# Controller.net
KiCad netlist of a schematic drawn in Altium Designer
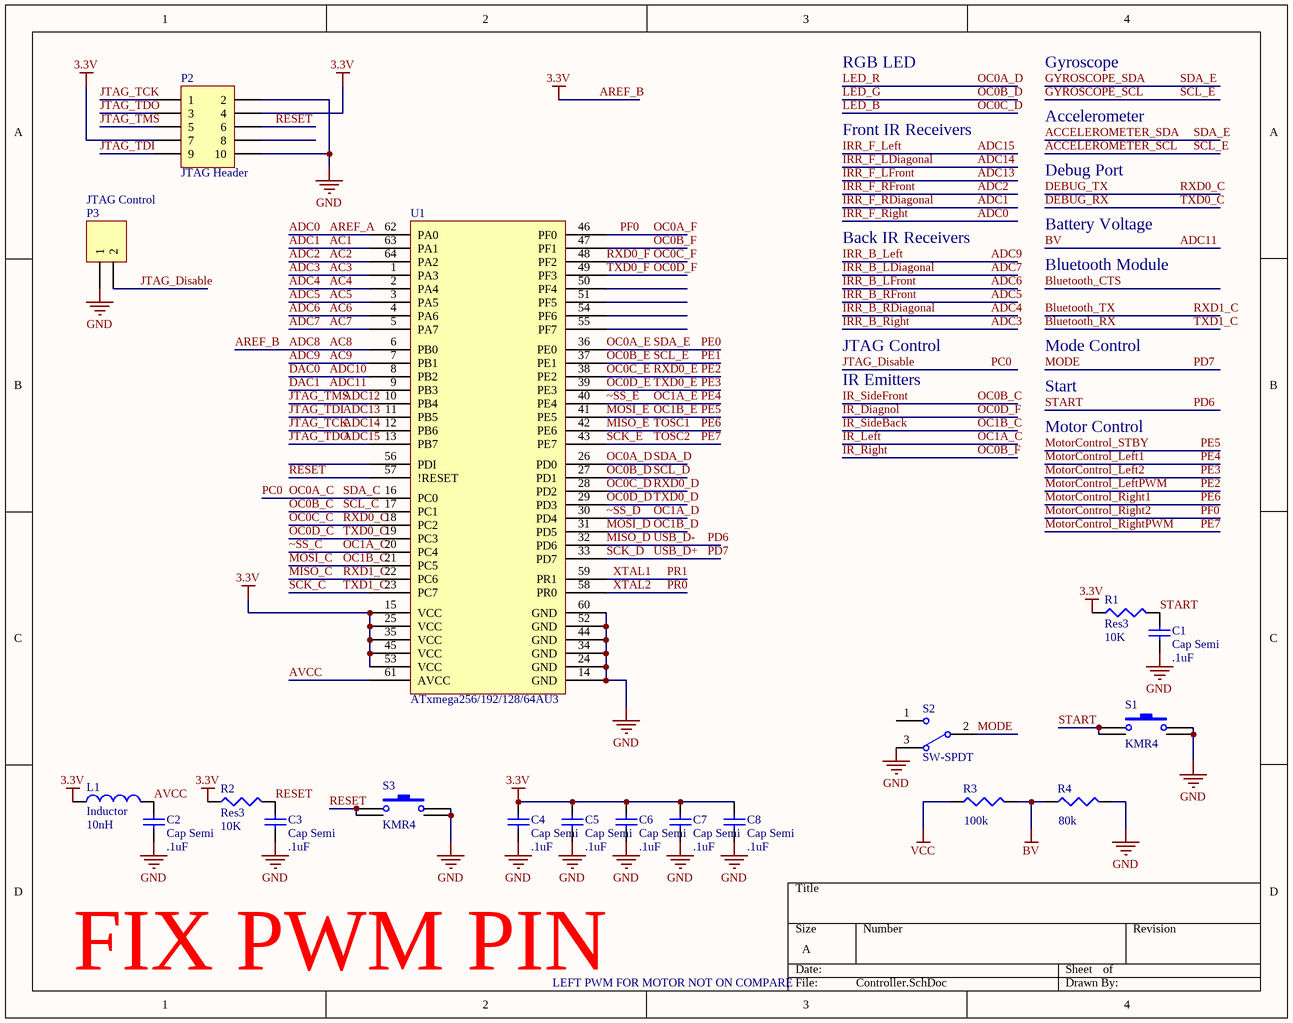
[diagram p0: Controller.SchDoc]

(export (version "E")
  (design (tool "Eeschema 10.0.6"))
  (components
    (comp (ref "C1")
      (value "Cap Semi")
      (footprint "1608[0603]")
      (description "Capacitor (Semiconductor SIM Model)")
      (fields (field (name "ALTIUM_VALUE") ".1uF") (field (name "PUBLISHER") "Altium Limited"))
      (libsource (lib "Miscellaneous Devices") (part "Cap Semi"))
    )
    (comp (ref "C2")
      (value "Cap Semi")
      (footprint "1608[0603]")
      (description "Capacitor (Semiconductor SIM Model)")
      (fields (field (name "ALTIUM_VALUE") ".1uF") (field (name "PUBLISHER") "Altium Limited"))
      (libsource (lib "Miscellaneous Devices") (part "Cap Semi"))
    )
    (comp (ref "C3")
      (value "Cap Semi")
      (footprint "1608[0603]")
      (description "Capacitor (Semiconductor SIM Model)")
      (fields (field (name "ALTIUM_VALUE") ".1uF") (field (name "PUBLISHER") "Altium Limited"))
      (libsource (lib "Miscellaneous Devices") (part "Cap Semi"))
    )
    (comp (ref "C4")
      (value "Cap Semi")
      (footprint "1608[0603]")
      (description "Capacitor (Semiconductor SIM Model)")
      (fields (field (name "ALTIUM_VALUE") ".1uF") (field (name "PUBLISHER") "Altium Limited"))
      (libsource (lib "Miscellaneous Devices") (part "Cap Semi"))
    )
    (comp (ref "C5")
      (value "Cap Semi")
      (footprint "1608[0603]")
      (description "Capacitor (Semiconductor SIM Model)")
      (fields (field (name "ALTIUM_VALUE") ".1uF") (field (name "PUBLISHER") "Altium Limited"))
      (libsource (lib "Miscellaneous Devices") (part "Cap Semi"))
    )
    (comp (ref "C6")
      (value "Cap Semi")
      (footprint "1608[0603]")
      (description "Capacitor (Semiconductor SIM Model)")
      (fields (field (name "ALTIUM_VALUE") ".1uF") (field (name "PUBLISHER") "Altium Limited"))
      (libsource (lib "Miscellaneous Devices") (part "Cap Semi"))
    )
    (comp (ref "C7")
      (value "Cap Semi")
      (footprint "1608[0603]")
      (description "Capacitor (Semiconductor SIM Model)")
      (fields (field (name "ALTIUM_VALUE") ".1uF") (field (name "PUBLISHER") "Altium Limited"))
      (libsource (lib "Miscellaneous Devices") (part "Cap Semi"))
    )
    (comp (ref "C8")
      (value "Cap Semi")
      (footprint "1608[0603]")
      (description "Capacitor (Semiconductor SIM Model)")
      (fields (field (name "ALTIUM_VALUE") ".1uF") (field (name "PUBLISHER") "Altium Limited"))
      (libsource (lib "Miscellaneous Devices") (part "Cap Semi"))
    )
    (comp (ref "L1")
      (value "Inductor")
      (footprint "INDC1608L")
      (fields (field (name "ALTIUM_VALUE") "10nH") (field (name "PUBLISHER") "Altium Limited"))
      (libsource (lib "Miscellaneous Devices") (part "Inductor"))
    )
    (comp (ref "P2")
      (value "JTAG Header")
      (footprint "HDR2X5")
      (description "Header, 5-Pin, Dual row")
      (fields (field (name "PUBLISHER") "Altium Limited"))
      (libsource (lib "Miscellaneous Connectors") (part "Header 5X2"))
    )
    (comp (ref "P3")
      (value "JTAG Control")
      (footprint "HDR1X2")
      (description "Header, 2-Pin")
      (fields (field (name "PUBLISHER") "Altium Limited"))
      (libsource (lib "Miscellaneous Connectors") (part "Header 2"))
    )
    (comp (ref "R1")
      (value "Res3")
      (footprint "J1-0603")
      (description "Resistor")
      (fields (field (name "ALTIUM_VALUE") "10K") (field (name "PUBLISHER") "Altium Limited"))
      (libsource (lib "Miscellaneous Devices") (part "Res3"))
    )
    (comp (ref "R2")
      (value "Res3")
      (footprint "J1-0603")
      (description "Resistor")
      (fields (field (name "ALTIUM_VALUE") "10K") (field (name "PUBLISHER") "Altium Limited"))
      (libsource (lib "Miscellaneous Devices") (part "Res3"))
    )
    (comp (ref "R3")
      (value "100k")
      (footprint "J1-0603")
      (description "Resistor")
      (fields (field (name "Comment") "Res3") (field (name "PUBLISHER") "Altium Limited"))
      (libsource (lib "Miscellaneous Devices") (part "Res3"))
    )
    (comp (ref "R4")
      (value "80k")
      (footprint "J1-0603")
      (description "Resistor")
      (fields (field (name "Comment") "Res3") (field (name "PUBLISHER") "Altium Limited"))
      (libsource (lib "Miscellaneous Devices") (part "Res3"))
    )
    (comp (ref "S1")
      (value "KMR4")
      (footprint "KMR4")
      (description "Switch")
      (fields (field (name "PUBLISHER") "Altium Limited"))
      (libsource (lib "Dans_Library") (part "SPST Tactile Switch"))
    )
    (comp (ref "S2")
      (value "SW-SPDT")
      (footprint "SPDT Switch")
      (description "SPDT Subminiature Toggle Switch, Right Angle Mounting, Vertical Actuation")
      (fields (field (name "PUBLISHER") "Altium Limited"))
      (libsource (lib "SharedLibrary") (part "SW-SPDT"))
    )
    (comp (ref "S3")
      (value "KMR4")
      (footprint "KMR4")
      (description "Switch")
      (fields (field (name "PUBLISHER") "Altium Limited"))
      (libsource (lib "Dans_Library") (part "SPST Tactile Switch"))
    )
    (comp (ref "U1")
      (value "ATxmega256/192/128/64AU3")
      (footprint "TQFP80P1600X1600X120-64N")
      (libsource (lib "SharedLibrary") (part "ATxmega256/192/128/64A3U"))
    )
  )
  (nets
    (net (code "1") (name "/AC1") (class "Default")
      (node (ref "U1") (pin "63") (pinfunction "PA1_63") (pintype "passive"))
    )
    (net (code "2") (name "/AC2") (class "Default")
      (node (ref "U1") (pin "64") (pinfunction "PA2_64") (pintype "passive"))
    )
    (net (code "3") (name "/AC3") (class "Default")
      (node (ref "U1") (pin "1") (pinfunction "PA3_1") (pintype "passive"))
    )
    (net (code "4") (name "/AC4") (class "Default")
      (node (ref "U1") (pin "2") (pinfunction "PA4_2") (pintype "passive"))
    )
    (net (code "5") (name "/AC5") (class "Default")
      (node (ref "U1") (pin "3") (pinfunction "PA5_3") (pintype "passive"))
    )
    (net (code "6") (name "/AC6") (class "Default")
      (node (ref "U1") (pin "4") (pinfunction "PA6_4") (pintype "passive"))
    )
    (net (code "7") (name "/AC7") (class "Default")
      (node (ref "U1") (pin "5") (pinfunction "PA7_5") (pintype "passive"))
    )
    (net (code "8") (name "/AC9") (class "Default")
      (node (ref "U1") (pin "7") (pinfunction "PB1_7") (pintype "passive"))
    )
    (net (code "9") (name "/ACCELEROMETER_SCL") (class "Default")
      (node (ref "U1") (pin "37") (pinfunction "PE1_37") (pintype "passive"))
    )
    (net (code "10") (name "/ACCELEROMETER_SDA") (class "Default")
      (node (ref "U1") (pin "36") (pinfunction "PE0_36") (pintype "passive"))
    )
    (net (code "11") (name "/ADC0") (class "Default")
      (node (ref "U1") (pin "62") (pinfunction "PA0_62") (pintype "passive"))
    )
    (net (code "12") (name "/ADC10") (class "Default")
      (node (ref "U1") (pin "8") (pinfunction "PB2_8") (pintype "passive"))
    )
    (net (code "13") (name "/ADC12") (class "Default")
      (node (ref "P2") (pin "5") (pinfunction "5_5") (pintype "passive"))
      (node (ref "U1") (pin "10") (pinfunction "PB4_10") (pintype "passive"))
    )
    (net (code "14") (name "/ADC13") (class "Default")
      (node (ref "P2") (pin "9") (pinfunction "9_9") (pintype "passive"))
      (node (ref "U1") (pin "11") (pinfunction "PB5_11") (pintype "passive"))
    )
    (net (code "15") (name "/ADC14") (class "Default")
      (node (ref "P2") (pin "1") (pinfunction "1_1") (pintype "passive"))
      (node (ref "U1") (pin "12") (pinfunction "PB6_12") (pintype "passive"))
    )
    (net (code "16") (name "/ADC15") (class "Default")
      (node (ref "P2") (pin "3") (pinfunction "3_3") (pintype "passive"))
      (node (ref "U1") (pin "13") (pinfunction "PB7_13") (pintype "passive"))
    )
    (net (code "17") (name "/AVCC") (class "Default")
      (node (ref "C2") (pin "2") (pinfunction "2_2") (pintype "passive"))
      (node (ref "L1") (pin "2") (pinfunction "2_2") (pintype "passive"))
      (node (ref "U1") (pin "61") (pinfunction "AVCC_61") (pintype "passive"))
    )
    (net (code "19") (name "/Bluetooth_RX") (class "Default")
      (node (ref "U1") (pin "23") (pinfunction "PC7_23") (pintype "passive"))
    )
    (net (code "20") (name "/Bluetooth_TX") (class "Default")
      (node (ref "U1") (pin "22") (pinfunction "PC6_22") (pintype "passive"))
    )
    (net (code "21") (name "/DEBUG_RX") (class "Default")
      (node (ref "U1") (pin "19") (pinfunction "PC3_19") (pintype "passive"))
    )
    (net (code "22") (name "/DEBUG_TX") (class "Default")
      (node (ref "U1") (pin "18") (pinfunction "PC2_18") (pintype "passive"))
    )
    (net (code "23") (name "/IR_Diagnol") (class "Default")
      (node (ref "U1") (pin "49") (pinfunction "PF3_49") (pintype "passive"))
    )
    (net (code "24") (name "/IR_Left") (class "Default")
      (node (ref "U1") (pin "20") (pinfunction "PC4_20") (pintype "passive"))
    )
    (net (code "25") (name "/IR_Right") (class "Default")
      (node (ref "U1") (pin "47") (pinfunction "PF1_47") (pintype "passive"))
    )
    (net (code "26") (name "/IR_SideBack") (class "Default")
      (node (ref "U1") (pin "21") (pinfunction "PC5_21") (pintype "passive"))
    )
    (net (code "27") (name "/IR_SideFront") (class "Default")
      (node (ref "U1") (pin "17") (pinfunction "PC1_17") (pintype "passive"))
    )
    (net (code "28") (name "/JTAG_Disable") (class "Default")
      (node (ref "P3") (pin "2") (pinfunction "2_2") (pintype "passive"))
      (node (ref "U1") (pin "16") (pinfunction "PC0_16") (pintype "passive"))
    )
    (net (code "29") (name "/LED_B") (class "Default")
      (node (ref "U1") (pin "28") (pinfunction "PD2_28") (pintype "passive"))
    )
    (net (code "30") (name "/LED_G") (class "Default")
      (node (ref "U1") (pin "27") (pinfunction "PD1_27") (pintype "passive"))
    )
    (net (code "31") (name "/LED_R") (class "Default")
      (node (ref "U1") (pin "26") (pinfunction "PD0_26") (pintype "passive"))
    )
    (net (code "32") (name "/MISO_D") (class "Default")
      (node (ref "C1") (pin "2") (pinfunction "2_2") (pintype "passive"))
      (node (ref "R1") (pin "2") (pinfunction "2_2") (pintype "passive"))
      (node (ref "S1") (pin "1") (pinfunction "1_1") (pintype "passive"))
      (node (ref "S1") (pin "3") (pinfunction "3_3") (pintype "passive"))
      (node (ref "U1") (pin "32") (pinfunction "PD6_32") (pintype "passive"))
    )
    (net (code "33") (name "/MISO_E") (class "Default")
      (node (ref "U1") (pin "42") (pinfunction "PE6_42") (pintype "passive"))
    )
    (net (code "34") (name "/MODE") (class "Default")
      (node (ref "S2") (pin "2") (pinfunction "2_2") (pintype "passive"))
      (node (ref "U1") (pin "33") (pinfunction "PD7_33") (pintype "passive"))
    )
    (net (code "35") (name "/MOSI_D") (class "Default")
      (node (ref "U1") (pin "31") (pinfunction "PD5_31") (pintype "passive"))
    )
    (net (code "36") (name "/MOSI_E") (class "Default")
      (node (ref "U1") (pin "41") (pinfunction "PE5_41") (pintype "passive"))
    )
    (net (code "37") (name "/MotorControl_Left1") (class "Default")
      (node (ref "U1") (pin "40") (pinfunction "PE4_40") (pintype "passive"))
    )
    (net (code "38") (name "/MotorControl_Left2") (class "Default")
      (node (ref "U1") (pin "39") (pinfunction "PE3_39") (pintype "passive"))
    )
    (net (code "39") (name "/MotorControl_LeftPWM") (class "Default")
      (node (ref "U1") (pin "38") (pinfunction "PE2_38") (pintype "passive"))
    )
    (net (code "40") (name "/MotorControl_Right2") (class "Default")
      (node (ref "U1") (pin "46") (pinfunction "PF0_46") (pintype "passive"))
    )
    (net (code "41") (name "/MotorControl_RightPWM") (class "Default")
      (node (ref "U1") (pin "43") (pinfunction "PE7_43") (pintype "passive"))
    )
    (net (code "42") (name "/OC0C_F") (class "Default")
      (node (ref "U1") (pin "48") (pinfunction "PF2_48") (pintype "passive"))
    )
    (net (code "43") (name "/OC0D_D") (class "Default")
      (node (ref "U1") (pin "29") (pinfunction "PD3_29") (pintype "passive"))
    )
    (net (code "44") (name "/OC1A_D") (class "Default")
      (node (ref "U1") (pin "30") (pinfunction "PD4_30") (pintype "passive"))
    )
    (net (code "45") (name "/PR0") (class "Default")
      (node (ref "U1") (pin "58") (pinfunction "PR0_58") (pintype "passive"))
    )
    (net (code "46") (name "/PR1") (class "Default")
      (node (ref "U1") (pin "59") (pinfunction "PR1_59") (pintype "passive"))
    )
    (net (code "47") (name "/RESET") (class "Default")
      (node (ref "C3") (pin "2") (pinfunction "2_2") (pintype "passive"))
      (node (ref "P2") (pin "6") (pinfunction "6_6") (pintype "passive"))
      (node (ref "R2") (pin "2") (pinfunction "2_2") (pintype "passive"))
      (node (ref "S3") (pin "1") (pinfunction "1_1") (pintype "passive"))
      (node (ref "S3") (pin "3") (pinfunction "3_3") (pintype "passive"))
      (node (ref "U1") (pin "57") (pinfunction "!RESET_57") (pintype "passive"))
    )
    (net (code "48") (name "3.3V") (class "Default")
      (node (ref "C4") (pin "2") (pinfunction "2_2") (pintype "passive"))
      (node (ref "C5") (pin "2") (pinfunction "2_2") (pintype "passive"))
      (node (ref "C6") (pin "2") (pinfunction "2_2") (pintype "passive"))
      (node (ref "C7") (pin "2") (pinfunction "2_2") (pintype "passive"))
      (node (ref "C8") (pin "2") (pinfunction "2_2") (pintype "passive"))
      (node (ref "L1") (pin "1") (pinfunction "1_1") (pintype "passive"))
      (node (ref "P2") (pin "4") (pinfunction "4_4") (pintype "passive"))
      (node (ref "P2") (pin "7") (pinfunction "7_7") (pintype "passive"))
      (node (ref "R1") (pin "1") (pinfunction "1_1") (pintype "passive"))
      (node (ref "R2") (pin "1") (pinfunction "1_1") (pintype "passive"))
      (node (ref "U1") (pin "15") (pinfunction "VCC_15") (pintype "passive"))
      (node (ref "U1") (pin "25") (pinfunction "VCC_25") (pintype "passive"))
      (node (ref "U1") (pin "35") (pinfunction "VCC_35") (pintype "passive"))
      (node (ref "U1") (pin "45") (pinfunction "VCC_45") (pintype "passive"))
      (node (ref "U1") (pin "53") (pinfunction "VCC_53") (pintype "passive"))
      (node (ref "U1") (pin "6") (pinfunction "PB0_6") (pintype "passive"))
    )
    (net (code "49") (name "BV") (class "Default")
      (node (ref "R3") (pin "2") (pinfunction "2_2") (pintype "passive"))
      (node (ref "R4") (pin "1") (pinfunction "1_1") (pintype "passive"))
      (node (ref "U1") (pin "9") (pinfunction "PB3_9") (pintype "passive"))
    )
    (net (code "50") (name "GND") (class "Default")
      (node (ref "C1") (pin "1") (pinfunction "1_1") (pintype "passive"))
      (node (ref "C2") (pin "1") (pinfunction "1_1") (pintype "passive"))
      (node (ref "C3") (pin "1") (pinfunction "1_1") (pintype "passive"))
      (node (ref "C4") (pin "1") (pinfunction "1_1") (pintype "passive"))
      (node (ref "C5") (pin "1") (pinfunction "1_1") (pintype "passive"))
      (node (ref "C6") (pin "1") (pinfunction "1_1") (pintype "passive"))
      (node (ref "C7") (pin "1") (pinfunction "1_1") (pintype "passive"))
      (node (ref "C8") (pin "1") (pinfunction "1_1") (pintype "passive"))
      (node (ref "P2") (pin "10") (pinfunction "10_10") (pintype "passive"))
      (node (ref "P2") (pin "2") (pinfunction "2_2") (pintype "passive"))
      (node (ref "P3") (pin "1") (pinfunction "1_1") (pintype "passive"))
      (node (ref "R4") (pin "2") (pinfunction "2_2") (pintype "passive"))
      (node (ref "S1") (pin "2") (pinfunction "2_2") (pintype "passive"))
      (node (ref "S1") (pin "4") (pinfunction "4_4") (pintype "passive"))
      (node (ref "S2") (pin "3") (pinfunction "3_3") (pintype "passive"))
      (node (ref "S3") (pin "2") (pinfunction "2_2") (pintype "passive"))
      (node (ref "S3") (pin "4") (pinfunction "4_4") (pintype "passive"))
      (node (ref "U1") (pin "14") (pinfunction "GND_14") (pintype "passive"))
      (node (ref "U1") (pin "24") (pinfunction "GND_24") (pintype "passive"))
      (node (ref "U1") (pin "34") (pinfunction "GND_34") (pintype "passive"))
      (node (ref "U1") (pin "44") (pinfunction "GND_44") (pintype "passive"))
      (node (ref "U1") (pin "52") (pinfunction "GND_52") (pintype "passive"))
      (node (ref "U1") (pin "60") (pinfunction "GND_60") (pintype "passive"))
    )
    (net (code "51") (name "VCC") (class "Default")
      (node (ref "R3") (pin "1") (pinfunction "1_1") (pintype "passive"))
    )
    (net (code "52") (name "unconnected-(P2-Pad8)") (class "Default")
      (node (ref "P2") (pin "8") (pinfunction "8_8") (pintype "passive"))
    )
    (net (code "53") (name "unconnected-(S2-Pad1)") (class "Default")
      (node (ref "S2") (pin "1") (pinfunction "1_1") (pintype "passive"))
    )
    (net (code "54") (name "unconnected-(U1-PDI-Pad56)") (class "Default")
      (node (ref "U1") (pin "56") (pinfunction "PDI_56") (pintype "passive"))
    )
    (net (code "55") (name "unconnected-(U1-PF4-Pad50)") (class "Default")
      (node (ref "U1") (pin "50") (pinfunction "PF4_50") (pintype "passive"))
    )
    (net (code "56") (name "unconnected-(U1-PF5-Pad51)") (class "Default")
      (node (ref "U1") (pin "51") (pinfunction "PF5_51") (pintype "passive"))
    )
    (net (code "57") (name "unconnected-(U1-PF6-Pad54)") (class "Default")
      (node (ref "U1") (pin "54") (pinfunction "PF6_54") (pintype "passive"))
    )
    (net (code "58") (name "unconnected-(U1-PF7-Pad55)") (class "Default")
      (node (ref "U1") (pin "55") (pinfunction "PF7_55") (pintype "passive"))
    )
  )
)
